# Sheet1.net
KiCad netlist of a schematic drawn in Altium Designer
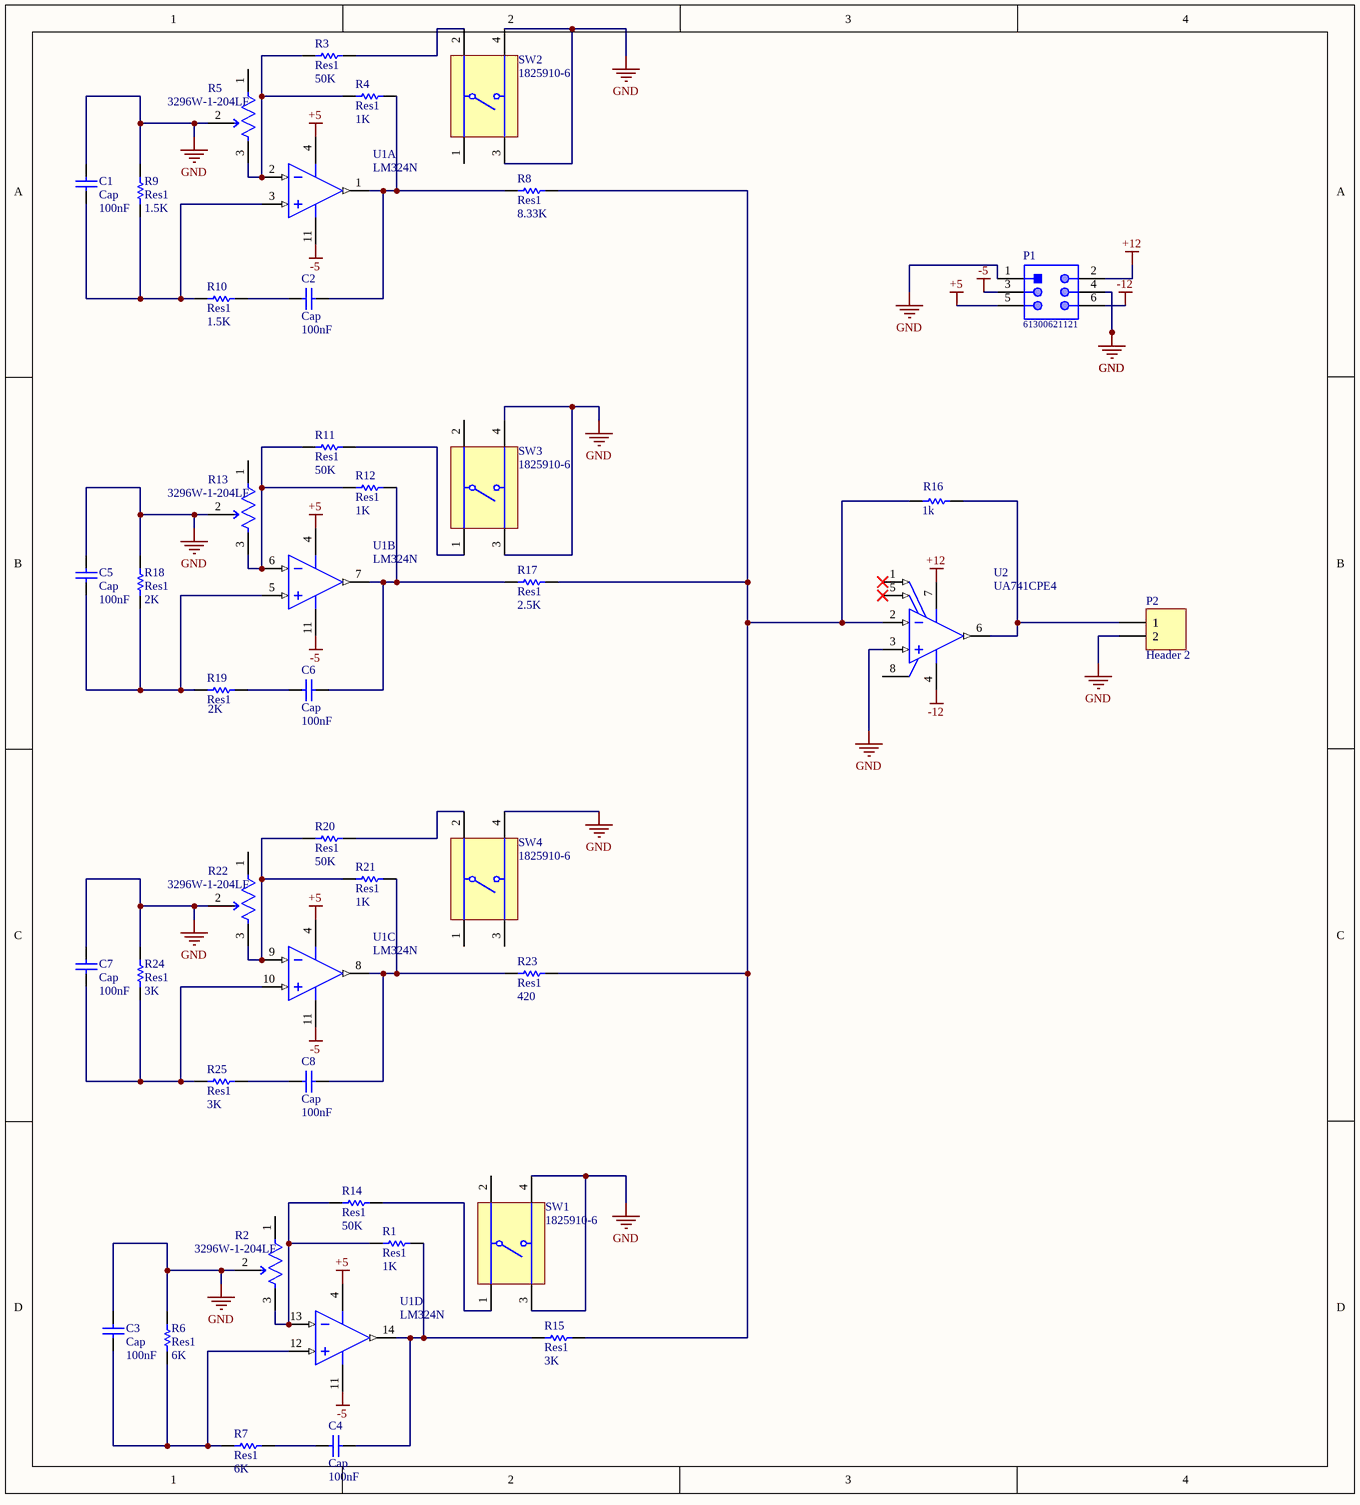
[diagram p0: Sheet1.SchDoc]

(export (version "E")
  (design (tool "Eeschema 10.0.6"))
  (components
    (comp (ref "C1")
      (value "Cap")
      (footprint "RAD-0.3")
      (description "Capacitor")
      (fields (field (name "ALTIUM_VALUE") "100nF") (field (name "PUBLISHER") "Altium Limited"))
      (libsource (lib "Miscellaneous Devices") (part "Cap"))
    )
    (comp (ref "C2")
      (value "Cap")
      (footprint "RAD-0.3")
      (description "Capacitor")
      (fields (field (name "ALTIUM_VALUE") "100nF") (field (name "PUBLISHER") "Altium Limited"))
      (libsource (lib "Miscellaneous Devices") (part "Cap"))
    )
    (comp (ref "C3")
      (value "Cap")
      (footprint "RAD-0.3")
      (description "Capacitor")
      (fields (field (name "ALTIUM_VALUE") "100nF") (field (name "PUBLISHER") "Altium Limited"))
      (libsource (lib "Miscellaneous Devices") (part "Cap"))
    )
    (comp (ref "C4")
      (value "Cap")
      (footprint "RAD-0.3")
      (description "Capacitor")
      (fields (field (name "ALTIUM_VALUE") "100nF") (field (name "PUBLISHER") "Altium Limited"))
      (libsource (lib "Miscellaneous Devices") (part "Cap"))
    )
    (comp (ref "C5")
      (value "Cap")
      (footprint "RAD-0.3")
      (description "Capacitor")
      (fields (field (name "ALTIUM_VALUE") "100nF") (field (name "PUBLISHER") "Altium Limited"))
      (libsource (lib "Miscellaneous Devices") (part "Cap"))
    )
    (comp (ref "C6")
      (value "Cap")
      (footprint "RAD-0.3")
      (description "Capacitor")
      (fields (field (name "ALTIUM_VALUE") "100nF") (field (name "PUBLISHER") "Altium Limited"))
      (libsource (lib "Miscellaneous Devices") (part "Cap"))
    )
    (comp (ref "C7")
      (value "Cap")
      (footprint "RAD-0.3")
      (description "Capacitor")
      (fields (field (name "ALTIUM_VALUE") "100nF") (field (name "PUBLISHER") "Altium Limited"))
      (libsource (lib "Miscellaneous Devices") (part "Cap"))
    )
    (comp (ref "C8")
      (value "Cap")
      (footprint "RAD-0.3")
      (description "Capacitor")
      (fields (field (name "ALTIUM_VALUE") "100nF") (field (name "PUBLISHER") "Altium Limited"))
      (libsource (lib "Miscellaneous Devices") (part "Cap"))
    )
    (comp (ref "P1")
      (value "61300621121")
      (footprint "61300621121")
      (description "THT Vertical Pin Header WR-PHD, Pitch 2.54 mm, Dual Row, 6 pins")
      (fields (field (name "MANUFACTURER") "Wurth Elektronik") (field (name "PUBLISHER") "WurthElektronik"))
      (libsource (lib "Altium Content Vault") (part "WE-CN-2P-M-R6"))
    )
    (comp (ref "P2")
      (value "Header 2")
      (footprint "HDR1X2")
      (description "Header, 2-Pin")
      (fields (field (name "PUBLISHER") "Altium Limited"))
      (libsource (lib "Miscellaneous Connectors") (part "Header 2"))
    )
    (comp (ref "R1")
      (value "Res1")
      (footprint "AXIAL-0.3")
      (description "Resistor")
      (fields (field (name "ALTIUM_VALUE") "1K") (field (name "PUBLISHER") "Altium Limited"))
      (libsource (lib "Miscellaneous Devices") (part "Res1"))
    )
    (comp (ref "R2")
      (value "3296W-1-204LF")
      (footprint "FP-3296W-MFG")
      (description "TRIMMER 200K OHM 0.5W PC PIN TOP")
      (fields (field (name "TOLERANCE") "10%"))
      (libsource (lib "Altium Content Vault") (part "2dcfd2547301a7d3209a5e99acfd772"))
    )
    (comp (ref "R3")
      (value "Res1")
      (footprint "AXIAL-0.3")
      (description "Resistor")
      (fields (field (name "ALTIUM_VALUE") "50K") (field (name "PUBLISHER") "Altium Limited"))
      (libsource (lib "Miscellaneous Devices") (part "Res1"))
    )
    (comp (ref "R4")
      (value "Res1")
      (footprint "AXIAL-0.3")
      (description "Resistor")
      (fields (field (name "ALTIUM_VALUE") "1K") (field (name "PUBLISHER") "Altium Limited"))
      (libsource (lib "Miscellaneous Devices") (part "Res1"))
    )
    (comp (ref "R5")
      (value "3296W-1-204LF")
      (footprint "FP-3296W-MFG")
      (description "TRIMMER 200K OHM 0.5W PC PIN TOP")
      (fields (field (name "TOLERANCE") "10%"))
      (libsource (lib "Altium Content Vault") (part "2dcfd2547301a7d3209a5e99acfd772"))
    )
    (comp (ref "R6")
      (value "Res1")
      (footprint "AXIAL-0.3")
      (description "Resistor")
      (fields (field (name "ALTIUM_VALUE") "6K") (field (name "PUBLISHER") "Altium Limited"))
      (libsource (lib "Miscellaneous Devices") (part "Res1"))
    )
    (comp (ref "R7")
      (value "Res1")
      (footprint "AXIAL-0.3")
      (description "Resistor")
      (fields (field (name "ALTIUM_VALUE") "6K") (field (name "PUBLISHER") "Altium Limited"))
      (libsource (lib "Miscellaneous Devices") (part "Res1"))
    )
    (comp (ref "R8")
      (value "Res1")
      (footprint "AXIAL-0.3")
      (description "Resistor")
      (fields (field (name "ALTIUM_VALUE") "8.33K") (field (name "PUBLISHER") "Altium Limited"))
      (libsource (lib "Miscellaneous Devices") (part "Res1"))
    )
    (comp (ref "R9")
      (value "Res1")
      (footprint "AXIAL-0.3")
      (description "Resistor")
      (fields (field (name "ALTIUM_VALUE") "1.5K") (field (name "PUBLISHER") "Altium Limited"))
      (libsource (lib "Miscellaneous Devices") (part "Res1"))
    )
    (comp (ref "R10")
      (value "Res1")
      (footprint "AXIAL-0.3")
      (description "Resistor")
      (fields (field (name "ALTIUM_VALUE") "1.5K") (field (name "PUBLISHER") "Altium Limited"))
      (libsource (lib "Miscellaneous Devices") (part "Res1"))
    )
    (comp (ref "R11")
      (value "Res1")
      (footprint "AXIAL-0.3")
      (description "Resistor")
      (fields (field (name "ALTIUM_VALUE") "50K") (field (name "PUBLISHER") "Altium Limited"))
      (libsource (lib "Miscellaneous Devices") (part "Res1"))
    )
    (comp (ref "R12")
      (value "Res1")
      (footprint "AXIAL-0.3")
      (description "Resistor")
      (fields (field (name "ALTIUM_VALUE") "1K") (field (name "PUBLISHER") "Altium Limited"))
      (libsource (lib "Miscellaneous Devices") (part "Res1"))
    )
    (comp (ref "R13")
      (value "3296W-1-204LF")
      (footprint "FP-3296W-MFG")
      (description "TRIMMER 200K OHM 0.5W PC PIN TOP")
      (fields (field (name "TOLERANCE") "10%"))
      (libsource (lib "Altium Content Vault") (part "2dcfd2547301a7d3209a5e99acfd772"))
    )
    (comp (ref "R14")
      (value "Res1")
      (footprint "AXIAL-0.3")
      (description "Resistor")
      (fields (field (name "ALTIUM_VALUE") "50K") (field (name "PUBLISHER") "Altium Limited"))
      (libsource (lib "Miscellaneous Devices") (part "Res1"))
    )
    (comp (ref "R15")
      (value "Res1")
      (footprint "AXIAL-0.3")
      (description "Resistor")
      (fields (field (name "ALTIUM_VALUE") "3K") (field (name "PUBLISHER") "Altium Limited"))
      (libsource (lib "Miscellaneous Devices") (part "Res1"))
    )
    (comp (ref "R16")
      (value "1k")
      (footprint "RESA86-1060X240")
      (description "Axial Resistor, 50 mOhm, +/- 1%, 2 W, -55 to 275 degC, 2-Pin THD, RoHS, Bulk")
      (libsource (lib "Altium Content Vault") (part "RES-2"))
    )
    (comp (ref "R17")
      (value "Res1")
      (footprint "AXIAL-0.3")
      (description "Resistor")
      (fields (field (name "ALTIUM_VALUE") "2.5K") (field (name "PUBLISHER") "Altium Limited"))
      (libsource (lib "Miscellaneous Devices") (part "Res1"))
    )
    (comp (ref "R18")
      (value "Res1")
      (footprint "AXIAL-0.3")
      (description "Resistor")
      (fields (field (name "ALTIUM_VALUE") "2K") (field (name "PUBLISHER") "Altium Limited"))
      (libsource (lib "Miscellaneous Devices") (part "Res1"))
    )
    (comp (ref "R19")
      (value "Res1")
      (footprint "AXIAL-0.3")
      (description "Resistor")
      (fields (field (name "ALTIUM_VALUE") "2K") (field (name "PUBLISHER") "Altium Limited"))
      (libsource (lib "Miscellaneous Devices") (part "Res1"))
    )
    (comp (ref "R20")
      (value "Res1")
      (footprint "AXIAL-0.3")
      (description "Resistor")
      (fields (field (name "ALTIUM_VALUE") "50K") (field (name "PUBLISHER") "Altium Limited"))
      (libsource (lib "Miscellaneous Devices") (part "Res1"))
    )
    (comp (ref "R21")
      (value "Res1")
      (footprint "AXIAL-0.3")
      (description "Resistor")
      (fields (field (name "ALTIUM_VALUE") "1K") (field (name "PUBLISHER") "Altium Limited"))
      (libsource (lib "Miscellaneous Devices") (part "Res1"))
    )
    (comp (ref "R22")
      (value "3296W-1-204LF")
      (footprint "FP-3296W-MFG")
      (description "TRIMMER 200K OHM 0.5W PC PIN TOP")
      (fields (field (name "TOLERANCE") "10%"))
      (libsource (lib "Altium Content Vault") (part "2dcfd2547301a7d3209a5e99acfd772"))
    )
    (comp (ref "R23")
      (value "Res1")
      (footprint "AXIAL-0.3")
      (description "Resistor")
      (fields (field (name "ALTIUM_VALUE") "420") (field (name "PUBLISHER") "Altium Limited"))
      (libsource (lib "Miscellaneous Devices") (part "Res1"))
    )
    (comp (ref "R24")
      (value "Res1")
      (footprint "AXIAL-0.3")
      (description "Resistor")
      (fields (field (name "ALTIUM_VALUE") "3K") (field (name "PUBLISHER") "Altium Limited"))
      (libsource (lib "Miscellaneous Devices") (part "Res1"))
    )
    (comp (ref "R25")
      (value "Res1")
      (footprint "AXIAL-0.3")
      (description "Resistor")
      (fields (field (name "ALTIUM_VALUE") "3K") (field (name "PUBLISHER") "Altium Limited"))
      (libsource (lib "Miscellaneous Devices") (part "Res1"))
    )
    (comp (ref "SW1")
      (value "1825910-6")
      (footprint "TECO-1825910-6_V")
      (description "Tact Switch, SPST-NO, 0.05 A, -35 to 85 degC, 4-Pin THD, RoHS, Bulk")
      (fields (field (name "MANUFACTURER") "TE Connectivity"))
      (libsource (lib "Altium Content Vault") (part "SW-SPST-4_A"))
    )
    (comp (ref "SW2")
      (value "1825910-6")
      (footprint "TECO-1825910-6_V")
      (description "Tact Switch, SPST-NO, 0.05 A, -35 to 85 degC, 4-Pin THD, RoHS, Bulk")
      (fields (field (name "MANUFACTURER") "TE Connectivity"))
      (libsource (lib "Altium Content Vault") (part "SW-SPST-4_A"))
    )
    (comp (ref "SW3")
      (value "1825910-6")
      (footprint "TECO-1825910-6_V")
      (description "Tact Switch, SPST-NO, 0.05 A, -35 to 85 degC, 4-Pin THD, RoHS, Bulk")
      (fields (field (name "MANUFACTURER") "TE Connectivity"))
      (libsource (lib "Altium Content Vault") (part "SW-SPST-4_A"))
    )
    (comp (ref "SW4")
      (value "1825910-6")
      (footprint "TECO-1825910-6_V")
      (description "Tact Switch, SPST-NO, 0.05 A, -35 to 85 degC, 4-Pin THD, RoHS, Bulk")
      (fields (field (name "MANUFACTURER") "TE Connectivity"))
      (libsource (lib "Altium Content Vault") (part "SW-SPST-4_A"))
    )
    (comp (ref "U1")
      (value "LM324N")
      (footprint "N0014A")
      (description "Low Power Quad Operational Amplifier, 14-pin MDIP")
      (fields (field (name "MANUFACTURER") "Texas Instruments"))
      (libsource (lib "Altium Content Vault") (part "AMP-OPA-LM124-14"))
    )
    (comp (ref "U2")
      (value "UA741CPE4")
      (footprint "TI-P8")
      (description "General-Purpose Operational Amplifier, 7 to 36 V, 0 to 70 degC, 8-pin DIP (P8), Pb-Free (RoHS)")
      (fields (field (name "MANUFACTURER") "Texas Instruments"))
      (libsource (lib "Altium Content Vault") (part "TI-AMP-S5-2-8"))
    )
  )
  (nets
    (net (code "1") (name "+5") (class "Default")
      (node (ref "P1") (pin "5") (pinfunction "5_5") (pintype "passive"))
      (node (ref "U1") (pin "4") (pinfunction "V+_4") (pintype "power_in"))
    )
    (net (code "2") (name "+12") (class "Default")
      (node (ref "P1") (pin "2") (pinfunction "2_2") (pintype "passive"))
      (node (ref "U2") (pin "7") (pinfunction "VCC+_7") (pintype "power_in"))
    )
    (net (code "3") (name "-5") (class "Default")
      (node (ref "P1") (pin "3") (pinfunction "3_3") (pintype "passive"))
      (node (ref "U1") (pin "11") (pinfunction "GND_11") (pintype "power_in"))
    )
    (net (code "4") (name "-12") (class "Default")
      (node (ref "P1") (pin "6") (pinfunction "6_6") (pintype "passive"))
      (node (ref "U2") (pin "4") (pinfunction "VCC-_4") (pintype "power_in"))
    )
    (net (code "5") (name "GND") (class "Default")
      (node (ref "C1") (pin "2") (pinfunction "2_2") (pintype "passive"))
      (node (ref "C3") (pin "2") (pinfunction "2_2") (pintype "passive"))
      (node (ref "C5") (pin "2") (pinfunction "2_2") (pintype "passive"))
      (node (ref "C7") (pin "2") (pinfunction "2_2") (pintype "passive"))
      (node (ref "P1") (pin "1") (pinfunction "1_1") (pintype "passive"))
      (node (ref "P1") (pin "4") (pinfunction "4_4") (pintype "passive"))
      (node (ref "P2") (pin "2") (pinfunction "2_2") (pintype "passive"))
      (node (ref "R13") (pin "2") (pinfunction "WIPER_2") (pintype "passive"))
      (node (ref "R18") (pin "2") (pinfunction "2_2") (pintype "passive"))
      (node (ref "R2") (pin "2") (pinfunction "WIPER_2") (pintype "passive"))
      (node (ref "R22") (pin "2") (pinfunction "WIPER_2") (pintype "passive"))
      (node (ref "R24") (pin "2") (pinfunction "2_2") (pintype "passive"))
      (node (ref "R5") (pin "2") (pinfunction "WIPER_2") (pintype "passive"))
      (node (ref "R6") (pin "2") (pinfunction "2_2") (pintype "passive"))
      (node (ref "R9") (pin "2") (pinfunction "2_2") (pintype "passive"))
      (node (ref "SW1") (pin "3") (pinfunction "3_3") (pintype "passive"))
      (node (ref "SW1") (pin "4") (pinfunction "4_4") (pintype "passive"))
      (node (ref "SW2") (pin "3") (pinfunction "3_3") (pintype "passive"))
      (node (ref "SW2") (pin "4") (pinfunction "4_4") (pintype "passive"))
      (node (ref "SW3") (pin "3") (pinfunction "3_3") (pintype "passive"))
      (node (ref "SW3") (pin "4") (pinfunction "4_4") (pintype "passive"))
      (node (ref "SW4") (pin "4") (pinfunction "4_4") (pintype "passive"))
      (node (ref "U2") (pin "3") (pinfunction "IN+_3") (pintype "input"))
    )
    (net (code "6") (name "Net-(C2-Pad1)") (class "Default")
      (node (ref "C2") (pin "1") (pinfunction "1_1") (pintype "passive"))
      (node (ref "R10") (pin "2") (pinfunction "2_2") (pintype "passive"))
    )
    (net (code "7") (name "Net-(C4-Pad1)") (class "Default")
      (node (ref "C4") (pin "1") (pinfunction "1_1") (pintype "passive"))
      (node (ref "R7") (pin "2") (pinfunction "2_2") (pintype "passive"))
    )
    (net (code "8") (name "Net-(C6-Pad1)") (class "Default")
      (node (ref "C6") (pin "1") (pinfunction "1_1") (pintype "passive"))
      (node (ref "R19") (pin "2") (pinfunction "2_2") (pintype "passive"))
    )
    (net (code "9") (name "Net-(C8-Pad1)") (class "Default")
      (node (ref "C8") (pin "1") (pinfunction "1_1") (pintype "passive"))
      (node (ref "R25") (pin "2") (pinfunction "2_2") (pintype "passive"))
    )
    (net (code "10") (name "Net-(R2-CW)") (class "Default")
      (node (ref "R1") (pin "2") (pinfunction "2_2") (pintype "passive"))
      (node (ref "R14") (pin "2") (pinfunction "2_2") (pintype "passive"))
      (node (ref "R2") (pin "3") (pinfunction "CW_3") (pintype "passive"))
      (node (ref "U1") (pin "13") (pinfunction "IN4-_13") (pintype "input"))
    )
    (net (code "11") (name "Net-(R3-Pad1)") (class "Default")
      (node (ref "R3") (pin "1") (pinfunction "1_1") (pintype "passive"))
      (node (ref "SW2") (pin "2") (pinfunction "2_2") (pintype "passive"))
    )
    (net (code "12") (name "Net-(R5-CW)") (class "Default")
      (node (ref "R3") (pin "2") (pinfunction "2_2") (pintype "passive"))
      (node (ref "R4") (pin "2") (pinfunction "2_2") (pintype "passive"))
      (node (ref "R5") (pin "3") (pinfunction "CW_3") (pintype "passive"))
      (node (ref "U1") (pin "2") (pinfunction "IN1-_2") (pintype "input"))
    )
    (net (code "13") (name "Net-(R11-Pad1)") (class "Default")
      (node (ref "R11") (pin "1") (pinfunction "1_1") (pintype "passive"))
      (node (ref "SW3") (pin "1") (pinfunction "1_1") (pintype "passive"))
    )
    (net (code "14") (name "Net-(R13-CW)") (class "Default")
      (node (ref "R11") (pin "2") (pinfunction "2_2") (pintype "passive"))
      (node (ref "R12") (pin "2") (pinfunction "2_2") (pintype "passive"))
      (node (ref "R13") (pin "3") (pinfunction "CW_3") (pintype "passive"))
      (node (ref "U1") (pin "6") (pinfunction "IN2-_6") (pintype "input"))
    )
    (net (code "15") (name "Net-(R14-Pad1)") (class "Default")
      (node (ref "R14") (pin "1") (pinfunction "1_1") (pintype "passive"))
      (node (ref "SW1") (pin "1") (pinfunction "1_1") (pintype "passive"))
    )
    (net (code "16") (name "Net-(R20-Pad1)") (class "Default")
      (node (ref "R20") (pin "1") (pinfunction "1_1") (pintype "passive"))
      (node (ref "SW4") (pin "2") (pinfunction "2_2") (pintype "passive"))
    )
    (net (code "17") (name "Net-(R22-CW)") (class "Default")
      (node (ref "R20") (pin "2") (pinfunction "2_2") (pintype "passive"))
      (node (ref "R21") (pin "2") (pinfunction "2_2") (pintype "passive"))
      (node (ref "R22") (pin "3") (pinfunction "CW_3") (pintype "passive"))
      (node (ref "U1") (pin "9") (pinfunction "IN3-_9") (pintype "input"))
    )
    (net (code "18") (name "Net-(U1A-IN1+)") (class "Default")
      (node (ref "C1") (pin "1") (pinfunction "1_1") (pintype "passive"))
      (node (ref "R10") (pin "1") (pinfunction "1_1") (pintype "passive"))
      (node (ref "R9") (pin "1") (pinfunction "1_1") (pintype "passive"))
      (node (ref "U1") (pin "3") (pinfunction "IN1+_3") (pintype "input"))
    )
    (net (code "19") (name "Net-(U1A-OUT1)") (class "Default")
      (node (ref "C2") (pin "2") (pinfunction "2_2") (pintype "passive"))
      (node (ref "R4") (pin "1") (pinfunction "1_1") (pintype "passive"))
      (node (ref "R8") (pin "2") (pinfunction "2_2") (pintype "passive"))
      (node (ref "U1") (pin "1") (pinfunction "OUT1_1") (pintype "output"))
    )
    (net (code "20") (name "Net-(U1B-IN2+)") (class "Default")
      (node (ref "C5") (pin "1") (pinfunction "1_1") (pintype "passive"))
      (node (ref "R18") (pin "1") (pinfunction "1_1") (pintype "passive"))
      (node (ref "R19") (pin "1") (pinfunction "1_1") (pintype "passive"))
      (node (ref "U1") (pin "5") (pinfunction "IN2+_5") (pintype "input"))
    )
    (net (code "21") (name "Net-(U1B-OUT2)") (class "Default")
      (node (ref "C6") (pin "2") (pinfunction "2_2") (pintype "passive"))
      (node (ref "R12") (pin "1") (pinfunction "1_1") (pintype "passive"))
      (node (ref "R17") (pin "2") (pinfunction "2_2") (pintype "passive"))
      (node (ref "U1") (pin "7") (pinfunction "OUT2_7") (pintype "output"))
    )
    (net (code "22") (name "Net-(U1C-IN3+)") (class "Default")
      (node (ref "C7") (pin "1") (pinfunction "1_1") (pintype "passive"))
      (node (ref "R24") (pin "1") (pinfunction "1_1") (pintype "passive"))
      (node (ref "R25") (pin "1") (pinfunction "1_1") (pintype "passive"))
      (node (ref "U1") (pin "10") (pinfunction "IN3+_10") (pintype "input"))
    )
    (net (code "23") (name "Net-(U1C-OUT3)") (class "Default")
      (node (ref "C8") (pin "2") (pinfunction "2_2") (pintype "passive"))
      (node (ref "R21") (pin "1") (pinfunction "1_1") (pintype "passive"))
      (node (ref "R23") (pin "2") (pinfunction "2_2") (pintype "passive"))
      (node (ref "U1") (pin "8") (pinfunction "OUT3_8") (pintype "output"))
    )
    (net (code "24") (name "Net-(U1D-IN4+)") (class "Default")
      (node (ref "C3") (pin "1") (pinfunction "1_1") (pintype "passive"))
      (node (ref "R6") (pin "1") (pinfunction "1_1") (pintype "passive"))
      (node (ref "R7") (pin "1") (pinfunction "1_1") (pintype "passive"))
      (node (ref "U1") (pin "12") (pinfunction "IN4+_12") (pintype "input"))
    )
    (net (code "25") (name "Net-(U1D-OUT4)") (class "Default")
      (node (ref "C4") (pin "2") (pinfunction "2_2") (pintype "passive"))
      (node (ref "R1") (pin "1") (pinfunction "1_1") (pintype "passive"))
      (node (ref "R15") (pin "2") (pinfunction "2_2") (pintype "passive"))
      (node (ref "U1") (pin "14") (pinfunction "OUT4_14") (pintype "output"))
    )
    (net (code "26") (name "Net-(U2-IN-)") (class "Default")
      (node (ref "R15") (pin "1") (pinfunction "1_1") (pintype "passive"))
      (node (ref "R16") (pin "1") (pinfunction "1_1") (pintype "passive"))
      (node (ref "R17") (pin "1") (pinfunction "1_1") (pintype "passive"))
      (node (ref "R23") (pin "1") (pinfunction "1_1") (pintype "passive"))
      (node (ref "R8") (pin "1") (pinfunction "1_1") (pintype "passive"))
      (node (ref "U2") (pin "2") (pinfunction "IN-_2") (pintype "input"))
    )
    (net (code "27") (name "Net-(U2-OUT)") (class "Default")
      (node (ref "P2") (pin "1") (pinfunction "1_1") (pintype "passive"))
      (node (ref "R16") (pin "2") (pinfunction "2_2") (pintype "passive"))
      (node (ref "U2") (pin "6") (pinfunction "OUT_6") (pintype "output"))
    )
    (net (code "28") (name "unconnected-(R2-CCW-Pad1)") (class "Default")
      (node (ref "R2") (pin "1") (pinfunction "CCW_1") (pintype "passive"))
    )
    (net (code "29") (name "unconnected-(R5-CCW-Pad1)") (class "Default")
      (node (ref "R5") (pin "1") (pinfunction "CCW_1") (pintype "passive"))
    )
    (net (code "30") (name "unconnected-(R13-CCW-Pad1)") (class "Default")
      (node (ref "R13") (pin "1") (pinfunction "CCW_1") (pintype "passive"))
    )
    (net (code "31") (name "unconnected-(R22-CCW-Pad1)") (class "Default")
      (node (ref "R22") (pin "1") (pinfunction "CCW_1") (pintype "passive"))
    )
    (net (code "32") (name "unconnected-(SW1-Pad2)") (class "Default")
      (node (ref "SW1") (pin "2") (pinfunction "2_2") (pintype "passive"))
    )
    (net (code "33") (name "unconnected-(SW2-Pad1)") (class "Default")
      (node (ref "SW2") (pin "1") (pinfunction "1_1") (pintype "passive"))
    )
    (net (code "34") (name "unconnected-(SW3-Pad2)") (class "Default")
      (node (ref "SW3") (pin "2") (pinfunction "2_2") (pintype "passive"))
    )
    (net (code "35") (name "unconnected-(SW4-Pad1)") (class "Default")
      (node (ref "SW4") (pin "1") (pinfunction "1_1") (pintype "passive"))
    )
    (net (code "36") (name "unconnected-(SW4-Pad3)") (class "Default")
      (node (ref "SW4") (pin "3") (pinfunction "3_3") (pintype "passive"))
    )
    (net (code "37") (name "unconnected-(U2-NC-Pad8)") (class "Default")
      (node (ref "U2") (pin "8") (pinfunction "NC_8") (pintype "passive"))
    )
    (net (code "38") (name "unconnected-(U2-OFFSET_N1-Pad1)") (class "Default")
      (node (ref "U2") (pin "1") (pinfunction "OFFSET_N1_1") (pintype "input+no_connect"))
    )
    (net (code "39") (name "unconnected-(U2-OFFSET_N2-Pad5)") (class "Default")
      (node (ref "U2") (pin "5") (pinfunction "OFFSET_N2_5") (pintype "input+no_connect"))
    )
  )
)
